# flash.net
KiCad netlist of a schematic drawn in Altium Designer
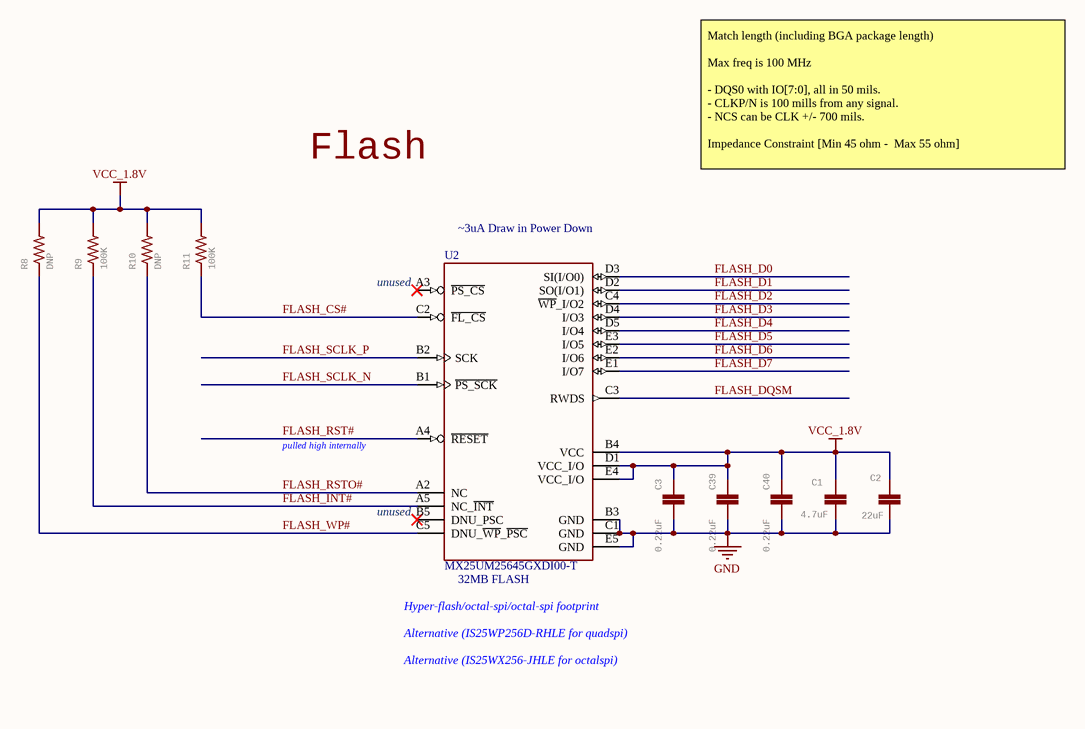
[diagram p0: flash.SchDoc]

(export (version "E")
  (design (tool "Eeschema 10.0.6"))
  (components
    (comp (ref "C1")
      (value "4.7uF")
      (footprint "0402-CAP")
      (description "CapacitorStandard 0603 ceramic capacitor, and 0.1\" leaded capacitor.")
      (fields (field (name "MPN") "JMK105BBJ475MV-F") (field (name "LIBRARYNAME") "sfe"))
      (libsource (lib "openmv-ae3") (part "CAP0402-CAP"))
    )
    (comp (ref "C2")
      (value "22uF")
      (footprint "0805")
      (fields (field (name "MPN") "CL21A226MQQNNNE"))
      (libsource (lib "openmv-ae3") (part "22UF-0805-6.3V-20%"))
    )
    (comp (ref "C3")
      (value "0.22uF")
      (footprint "C0201")
      (description "CAPACITOR, European symbol")
      (fields (field (name "MPN") "GRM033R60J224ME15D"))
      (libsource (lib "openmv-ae3") (part "C-EUC0201"))
    )
    (comp (ref "C39")
      (value "0.22uF")
      (footprint "C0201")
      (description "CAPACITOR, European symbol")
      (fields (field (name "MPN") "GRM033R60J224ME15D"))
      (libsource (lib "openmv-ae3") (part "C-EUC0201"))
    )
    (comp (ref "C40")
      (value "0.22uF")
      (footprint "C0201")
      (description "CAPACITOR, European symbol")
      (fields (field (name "MPN") "GRM033R60J224ME15D"))
      (libsource (lib "openmv-ae3") (part "C-EUC0201"))
    )
    (comp (ref "R8")
      (value "DNP")
      (footprint "R0201")
      (fields (field (name "LIBRARYNAME") "sfe"))
      (libsource (lib "openmv-ae3") (part "RESISTOR0402-RES"))
    )
    (comp (ref "R9")
      (value "100K")
      (footprint "R0201")
      (fields (field (name "MPN") "RMCF0201FT100K") (field (name "LIBRARYNAME") "sfe"))
      (libsource (lib "openmv-ae3") (part "RESISTOR0402-RES"))
    )
    (comp (ref "R10")
      (value "DNP")
      (footprint "R0201")
      (fields (field (name "LIBRARYNAME") "sfe"))
      (libsource (lib "openmv-ae3") (part "RESISTOR0402-RES"))
    )
    (comp (ref "R11")
      (value "100K")
      (footprint "R0201")
      (fields (field (name "MPN") "RMCF0201FT100K") (field (name "LIBRARYNAME") "sfe"))
      (libsource (lib "openmv-ae3") (part "RESISTOR0402-RES"))
    )
    (comp (ref "U2")
      (value "MX25UM25645GXDI00-T")
      (footprint "24-TBGA")
      (description "IC, Flash,32MB x 8, Octal SPI, Ind Temp, 1.8V,24-BGA")
      (fields (field (name "MF") "ISSI") (field (name "MPN") "MX25UM25645GXDI00-T"))
      (libsource (lib "openmv-ae3") (part "IS25WX256-JHLE"))
    )
  )
  (nets
    (net (code "1") (name "/FLASH_CS#") (class "Default")
      (node (ref "R11") (pin "1") (pinfunction "1_1") (pintype "passive"))
      (node (ref "U2") (pin "C2") (pinfunction "~{FL_CS}_C2") (pintype "input"))
    )
    (net (code "2") (name "/FLASH_D0") (class "Default")
      (node (ref "U2") (pin "D3") (pinfunction "SI(I/O0)_D3") (pintype "bidirectional"))
    )
    (net (code "3") (name "/FLASH_D1") (class "Default")
      (node (ref "U2") (pin "D2") (pinfunction "SO(I/O1)_D2") (pintype "bidirectional"))
    )
    (net (code "4") (name "/FLASH_D2") (class "Default")
      (node (ref "U2") (pin "C4") (pinfunction "~{WP}_I/O2_C4") (pintype "bidirectional"))
    )
    (net (code "5") (name "/FLASH_D3") (class "Default")
      (node (ref "U2") (pin "D4") (pinfunction "I/O3_D4") (pintype "bidirectional"))
    )
    (net (code "6") (name "/FLASH_D4") (class "Default")
      (node (ref "U2") (pin "D5") (pinfunction "I/O4_D5") (pintype "bidirectional"))
    )
    (net (code "7") (name "/FLASH_D5") (class "Default")
      (node (ref "U2") (pin "E3") (pinfunction "I/O5_E3") (pintype "bidirectional"))
    )
    (net (code "8") (name "/FLASH_D6") (class "Default")
      (node (ref "U2") (pin "E2") (pinfunction "I/O6_E2") (pintype "bidirectional"))
    )
    (net (code "9") (name "/FLASH_D7") (class "Default")
      (node (ref "U2") (pin "E1") (pinfunction "I/O7_E1") (pintype "bidirectional"))
    )
    (net (code "10") (name "/FLASH_DQSM") (class "Default")
      (node (ref "U2") (pin "C3") (pinfunction "RWDS_C3") (pintype "output"))
    )
    (net (code "11") (name "/FLASH_INT#") (class "Default")
      (node (ref "R9") (pin "1") (pinfunction "1_1") (pintype "passive"))
      (node (ref "U2") (pin "A5") (pinfunction "NC_~{INT}_A5") (pintype "passive"))
    )
    (net (code "12") (name "/FLASH_RST#") (class "Default")
      (node (ref "U2") (pin "A4") (pinfunction "~{RESET}_A4") (pintype "input"))
    )
    (net (code "13") (name "/FLASH_RSTO#") (class "Default")
      (node (ref "R10") (pin "1") (pinfunction "1_1") (pintype "passive"))
      (node (ref "U2") (pin "A2") (pinfunction "NC_A2") (pintype "passive"))
    )
    (net (code "14") (name "/FLASH_SCLK_N") (class "Default")
      (node (ref "U2") (pin "B1") (pinfunction "~{PS_SCK}_B1") (pintype "input"))
    )
    (net (code "15") (name "/FLASH_SCLK_P") (class "Default")
      (node (ref "U2") (pin "B2") (pinfunction "SCK_B2") (pintype "input"))
    )
    (net (code "16") (name "/FLASH_WP#") (class "Default")
      (node (ref "R8") (pin "1") (pinfunction "1_1") (pintype "passive"))
      (node (ref "U2") (pin "C5") (pinfunction "DNU_~{WP}_~{PSC}_C5") (pintype "passive"))
    )
    (net (code "17") (name "GND") (class "Default")
      (node (ref "C1") (pin "1") (pinfunction "1_1") (pintype "passive"))
      (node (ref "C2") (pin "1") (pinfunction "1_1") (pintype "passive"))
      (node (ref "C3") (pin "2") (pinfunction "2_2") (pintype "passive"))
      (node (ref "C39") (pin "2") (pinfunction "2_2") (pintype "passive"))
      (node (ref "C40") (pin "2") (pinfunction "2_2") (pintype "passive"))
      (node (ref "U2") (pin "B3") (pinfunction "GND_B3") (pintype "power_in"))
      (node (ref "U2") (pin "C1") (pinfunction "GND_C1") (pintype "power_in"))
      (node (ref "U2") (pin "E5") (pinfunction "GND_E5") (pintype "power_in"))
    )
    (net (code "18") (name "VCC_1.8V") (class "Default")
      (node (ref "C1") (pin "2") (pinfunction "2_2") (pintype "passive"))
      (node (ref "C2") (pin "2") (pinfunction "2_2") (pintype "passive"))
      (node (ref "C3") (pin "1") (pinfunction "1_1") (pintype "passive"))
      (node (ref "C39") (pin "1") (pinfunction "1_1") (pintype "passive"))
      (node (ref "C40") (pin "1") (pinfunction "1_1") (pintype "passive"))
      (node (ref "R10") (pin "2") (pinfunction "2_2") (pintype "passive"))
      (node (ref "R11") (pin "2") (pinfunction "2_2") (pintype "passive"))
      (node (ref "R8") (pin "2") (pinfunction "2_2") (pintype "passive"))
      (node (ref "R9") (pin "2") (pinfunction "2_2") (pintype "passive"))
      (node (ref "U2") (pin "B4") (pinfunction "VCC_B4") (pintype "power_in"))
      (node (ref "U2") (pin "D1") (pinfunction "VCC_I/O_D1") (pintype "power_in"))
      (node (ref "U2") (pin "E4") (pinfunction "VCC_I/O_E4") (pintype "power_in"))
    )
    (net (code "19") (name "unconnected-(U2-DNU_PSC-PadB5)") (class "Default")
      (node (ref "U2") (pin "B5") (pinfunction "DNU_PSC_B5") (pintype "passive+no_connect"))
    )
    (net (code "20") (name "unconnected-(U2-~{PS_CS}-PadA3)") (class "Default")
      (node (ref "U2") (pin "A3") (pinfunction "~{PS_CS}_A3") (pintype "input+no_connect"))
    )
  )
)
